# 5v_converter.net
KiCad netlist of a schematic drawn in EAGLE
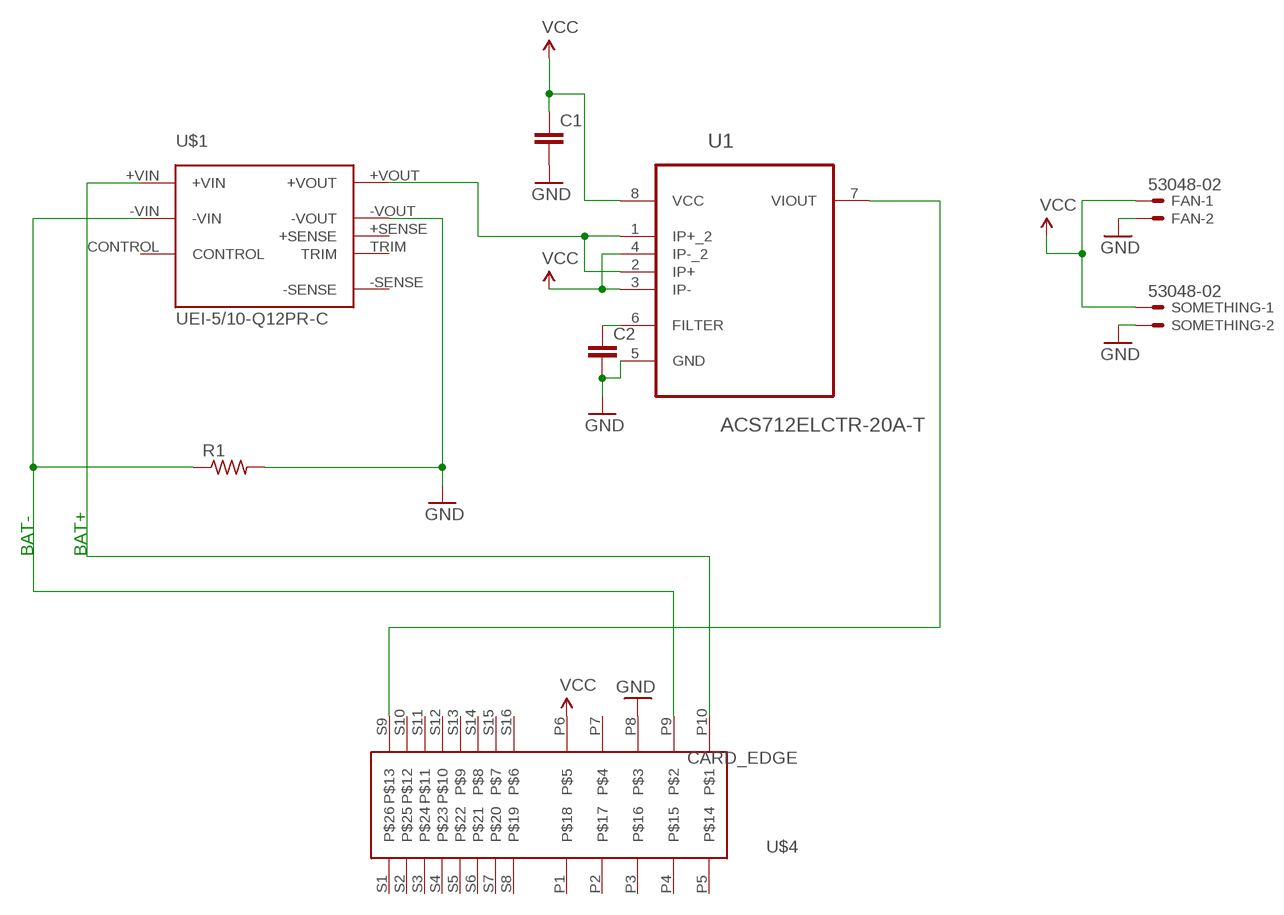
[diagram p0: schematic, sheet 1]

(export (version "E")
  (design (tool "Eeschema 10.0.6"))
  (components
    (comp (ref "C1")
      (value "C-EU025-024X044")
      (footprint "eagle-import:C025-024X044")
      (libsource (lib "eagle-import") (part "C-EU025-024X044"))
    )
    (comp (ref "C2")
      (value "C-EU025-024X044")
      (footprint "eagle-import:C025-024X044")
      (libsource (lib "eagle-import") (part "C-EU025-024X044"))
    )
    (comp (ref "FAN")
      (value "53048-02")
      (footprint "eagle-import:53048-02")
      (fields (field (name "MF") "MOLEX") (field (name "MPN") "53048-0210"))
      (libsource (lib "eagle-import") (part "53?-02048"))
    )
    (comp (ref "R1")
      (value "R-US_0204/2V")
      (footprint "eagle-import:0204V")
      (libsource (lib "eagle-import") (part "R-US_0204/2V"))
    )
    (comp (ref "SOMETHING")
      (value "53048-02")
      (footprint "eagle-import:53048-02")
      (fields (field (name "MF") "MOLEX") (field (name "MPN") "53048-0210"))
      (libsource (lib "eagle-import") (part "53?-02048"))
    )
    (comp (ref "U$1")
      (value "UEI-5/10-Q12PR-C")
      (footprint "eagle-import:UEI")
      (libsource (lib "eagle-import") (part "UEI-5/10-Q12PR-C"))
    )
    (comp (ref "U$4")
      (value "CARD_EDGE")
      (footprint "eagle-import:EDGE_CONNECTOR")
      (libsource (lib "eagle-import") (part "CARD_EDGE"))
    )
    (comp (ref "U1")
      (value "ACS712ELCTR-20A-T")
      (footprint "eagle-import:SOIC127P600X175-8N")
      (libsource (lib "eagle-import") (part "ACS712ELCTR-20A-T"))
    )
  )
  (nets
    (net (code "1") (name "GND") (class "Default")
      (node (ref "C1") (pin "2") (pinfunction "2_2") (pintype "passive"))
      (node (ref "C2") (pin "2") (pinfunction "2_2") (pintype "passive"))
      (node (ref "FAN") (pin "2") (pinfunction "S_2") (pintype "passive"))
      (node (ref "R1") (pin "2") (pinfunction "2_2") (pintype "passive"))
      (node (ref "SOMETHING") (pin "2") (pinfunction "S_2") (pintype "passive"))
      (node (ref "U$1") (pin "-VOUT") (pinfunction "-VOUT_-VOUT") (pintype "bidirectional"))
      (node (ref "U$4") (pin "P8") (pinfunction "P$3_P8") (pintype "bidirectional"))
      (node (ref "U1") (pin "5") (pinfunction "GND_5") (pintype "passive"))
    )
    (net (code "2") (name "Net-(U$4-P$1)") (class "Default")
      (node (ref "U$1") (pin "+VIN") (pinfunction "+VIN_+VIN") (pintype "bidirectional"))
      (node (ref "U$4") (pin "P10") (pinfunction "P$1_P10") (pintype "bidirectional"))
    )
    (net (code "3") (name "Net-(U$4-P$2)") (class "Default")
      (node (ref "R1") (pin "1") (pinfunction "1_1") (pintype "passive"))
      (node (ref "U$1") (pin "-VIN") (pinfunction "-VIN_-VIN") (pintype "bidirectional"))
      (node (ref "U$4") (pin "P9") (pinfunction "P$2_P9") (pintype "bidirectional"))
    )
    (net (code "4") (name "Net-(U$4-P$13)") (class "Default")
      (node (ref "U$4") (pin "S9") (pinfunction "P$13_S9") (pintype "bidirectional"))
      (node (ref "U1") (pin "7") (pinfunction "VIOUT_7") (pintype "output"))
    )
    (net (code "5") (name "Net-(U1-FILTER)") (class "Default")
      (node (ref "C2") (pin "1") (pinfunction "1_1") (pintype "passive"))
      (node (ref "U1") (pin "6") (pinfunction "FILTER_6") (pintype "input"))
    )
    (net (code "6") (name "Net-(U1-IP+)") (class "Default")
      (node (ref "U$1") (pin "+VOUT") (pinfunction "+VOUT_+VOUT") (pintype "bidirectional"))
      (node (ref "U1") (pin "1") (pinfunction "IP+_2_1") (pintype "input"))
      (node (ref "U1") (pin "2") (pinfunction "IP+_2") (pintype "input"))
    )
    (net (code "7") (name "VCC") (class "Default")
      (node (ref "C1") (pin "1") (pinfunction "1_1") (pintype "passive"))
      (node (ref "FAN") (pin "1") (pinfunction "S_1") (pintype "passive"))
      (node (ref "SOMETHING") (pin "1") (pinfunction "S_1") (pintype "passive"))
      (node (ref "U$4") (pin "P6") (pinfunction "P$5_P6") (pintype "bidirectional"))
      (node (ref "U1") (pin "3") (pinfunction "IP-_3") (pintype "input"))
      (node (ref "U1") (pin "4") (pinfunction "IP-_2_4") (pintype "input"))
      (node (ref "U1") (pin "8") (pinfunction "VCC_8") (pintype "power_in"))
    )
    (net (code "8") (name "unconnected-(U$1-Pad+SENSE)") (class "Default")
      (node (ref "U$1") (pin "+SENSE") (pinfunction "+SENSE_+SENSE") (pintype "bidirectional"))
    )
    (net (code "9") (name "unconnected-(U$1-Pad-SENSE)") (class "Default")
      (node (ref "U$1") (pin "-SENSE") (pinfunction "-SENSE_-SENSE") (pintype "bidirectional"))
    )
    (net (code "10") (name "unconnected-(U$1-PadCONTROL)") (class "Default")
      (node (ref "U$1") (pin "CONTROL") (pinfunction "CONTROL_CONTROL") (pintype "bidirectional"))
    )
    (net (code "11") (name "unconnected-(U$1-PadTRIM)") (class "Default")
      (node (ref "U$1") (pin "TRIM") (pinfunction "TRIM_TRIM") (pintype "bidirectional"))
    )
    (net (code "12") (name "unconnected-(U$4-P$4-PadP7)") (class "Default")
      (node (ref "U$4") (pin "P7") (pinfunction "P$4_P7") (pintype "bidirectional"))
    )
    (net (code "13") (name "unconnected-(U$4-P$6-PadS16)") (class "Default")
      (node (ref "U$4") (pin "S16") (pinfunction "P$6_S16") (pintype "bidirectional"))
    )
    (net (code "14") (name "unconnected-(U$4-P$7-PadS15)") (class "Default")
      (node (ref "U$4") (pin "S15") (pinfunction "P$7_S15") (pintype "bidirectional"))
    )
    (net (code "15") (name "unconnected-(U$4-P$8-PadS14)") (class "Default")
      (node (ref "U$4") (pin "S14") (pinfunction "P$8_S14") (pintype "bidirectional"))
    )
    (net (code "16") (name "unconnected-(U$4-P$9-PadS13)") (class "Default")
      (node (ref "U$4") (pin "S13") (pinfunction "P$9_S13") (pintype "bidirectional"))
    )
    (net (code "17") (name "unconnected-(U$4-P$10-PadS12)") (class "Default")
      (node (ref "U$4") (pin "S12") (pinfunction "P$10_S12") (pintype "bidirectional"))
    )
    (net (code "18") (name "unconnected-(U$4-P$11-PadS11)") (class "Default")
      (node (ref "U$4") (pin "S11") (pinfunction "P$11_S11") (pintype "bidirectional"))
    )
    (net (code "19") (name "unconnected-(U$4-P$12-PadS10)") (class "Default")
      (node (ref "U$4") (pin "S10") (pinfunction "P$12_S10") (pintype "bidirectional"))
    )
    (net (code "20") (name "unconnected-(U$4-P$14-PadP5)") (class "Default")
      (node (ref "U$4") (pin "P5") (pinfunction "P$14_P5") (pintype "bidirectional"))
    )
    (net (code "21") (name "unconnected-(U$4-P$15-PadP4)") (class "Default")
      (node (ref "U$4") (pin "P4") (pinfunction "P$15_P4") (pintype "bidirectional"))
    )
    (net (code "22") (name "unconnected-(U$4-P$16-PadP3)") (class "Default")
      (node (ref "U$4") (pin "P3") (pinfunction "P$16_P3") (pintype "bidirectional"))
    )
    (net (code "23") (name "unconnected-(U$4-P$17-PadP2)") (class "Default")
      (node (ref "U$4") (pin "P2") (pinfunction "P$17_P2") (pintype "bidirectional"))
    )
    (net (code "24") (name "unconnected-(U$4-P$18-PadP1)") (class "Default")
      (node (ref "U$4") (pin "P1") (pinfunction "P$18_P1") (pintype "bidirectional"))
    )
    (net (code "25") (name "unconnected-(U$4-P$19-PadS8)") (class "Default")
      (node (ref "U$4") (pin "S8") (pinfunction "P$19_S8") (pintype "bidirectional"))
    )
    (net (code "26") (name "unconnected-(U$4-P$20-PadS7)") (class "Default")
      (node (ref "U$4") (pin "S7") (pinfunction "P$20_S7") (pintype "bidirectional"))
    )
    (net (code "27") (name "unconnected-(U$4-P$21-PadS6)") (class "Default")
      (node (ref "U$4") (pin "S6") (pinfunction "P$21_S6") (pintype "bidirectional"))
    )
    (net (code "28") (name "unconnected-(U$4-P$22-PadS5)") (class "Default")
      (node (ref "U$4") (pin "S5") (pinfunction "P$22_S5") (pintype "bidirectional"))
    )
    (net (code "29") (name "unconnected-(U$4-P$23-PadS4)") (class "Default")
      (node (ref "U$4") (pin "S4") (pinfunction "P$23_S4") (pintype "bidirectional"))
    )
    (net (code "30") (name "unconnected-(U$4-P$24-PadS3)") (class "Default")
      (node (ref "U$4") (pin "S3") (pinfunction "P$24_S3") (pintype "bidirectional"))
    )
    (net (code "31") (name "unconnected-(U$4-P$25-PadS2)") (class "Default")
      (node (ref "U$4") (pin "S2") (pinfunction "P$25_S2") (pintype "bidirectional"))
    )
    (net (code "32") (name "unconnected-(U$4-P$26-PadS1)") (class "Default")
      (node (ref "U$4") (pin "S1") (pinfunction "P$26_S1") (pintype "bidirectional"))
    )
  )
)
